# INDICATOR_DISPLAY.net
KiCad netlist of a schematic drawn in Altium Designer
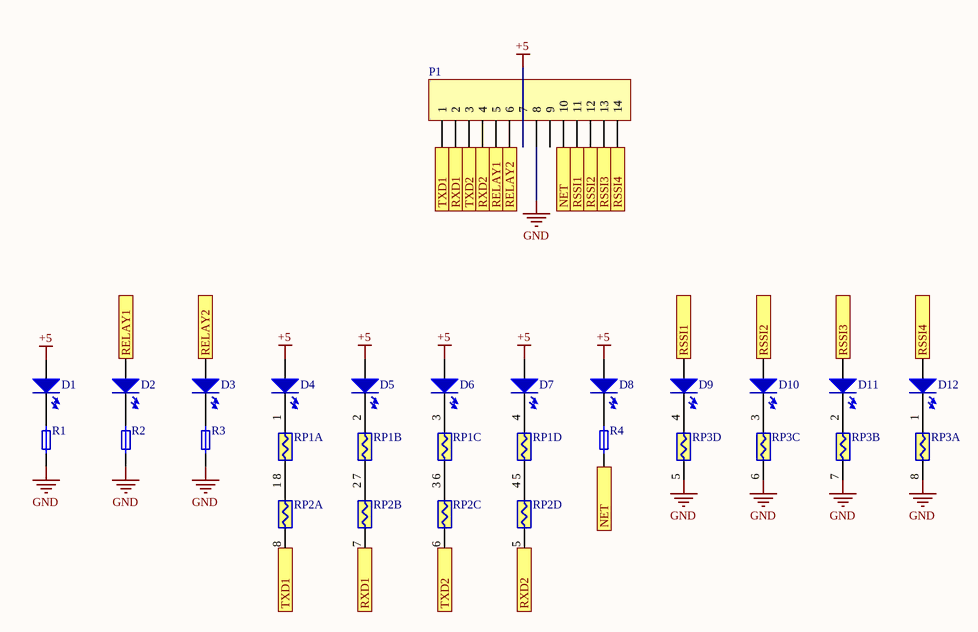
[diagram p0: INDICATOR DISPLAY.SchDoc]

(export (version "E")
  (design (tool "Eeschema 10.0.6"))
  (components
    (comp (ref "D1")
      (value "SMD LED")
      (footprint "LED RED 3MM S")
      (libsource (lib "MyLibrary") (part "LED SMD"))
    )
    (comp (ref "D2")
      (value "SMD LED")
      (footprint "LED RED 3MM S")
      (libsource (lib "MyLibrary") (part "LED SMD"))
    )
    (comp (ref "D3")
      (value "SMD LED")
      (footprint "LED RED 3MM S")
      (libsource (lib "MyLibrary") (part "LED SMD"))
    )
    (comp (ref "D4")
      (value "SMD LED")
      (footprint "LED RED 3MM S")
      (libsource (lib "MyLibrary") (part "LED SMD"))
    )
    (comp (ref "D5")
      (value "SMD LED")
      (footprint "LED RED 3MM S")
      (libsource (lib "MyLibrary") (part "LED SMD"))
    )
    (comp (ref "D6")
      (value "SMD LED")
      (footprint "LED RED 3MM S")
      (libsource (lib "MyLibrary") (part "LED SMD"))
    )
    (comp (ref "D7")
      (value "SMD LED")
      (footprint "LED RED 3MM S")
      (libsource (lib "MyLibrary") (part "LED SMD"))
    )
    (comp (ref "D8")
      (value "SMD LED")
      (footprint "LED RED 3MM S")
      (libsource (lib "MyLibrary") (part "LED SMD"))
    )
    (comp (ref "D9")
      (value "SMD LED")
      (footprint "LED RED 3MM S")
      (libsource (lib "MyLibrary") (part "LED SMD"))
    )
    (comp (ref "D10")
      (value "SMD LED")
      (footprint "LED RED 3MM S")
      (libsource (lib "MyLibrary") (part "LED SMD"))
    )
    (comp (ref "D11")
      (value "SMD LED")
      (footprint "LED RED 3MM S")
      (libsource (lib "MyLibrary") (part "LED SMD"))
    )
    (comp (ref "D12")
      (value "SMD LED")
      (footprint "LED RED 3MM S")
      (libsource (lib "MyLibrary") (part "LED SMD"))
    )
    (comp (ref "P1")
      (value "Header 14")
      (footprint "HDR1X14")
      (description "Header, 14-Pin")
      (fields (field (name "PUBLISHER") "Altium Limited"))
      (libsource (lib "Miscellaneous Connectors") (part "Header 14"))
    )
    (comp (ref "R1")
      (value "PTS120630V012")
      (footprint "1206 Resistor")
      (libsource (lib "MyLibrary") (part "PTS120630V012"))
    )
    (comp (ref "R2")
      (value "PTS120630V012")
      (footprint "1206 Resistor")
      (libsource (lib "MyLibrary") (part "PTS120630V012"))
    )
    (comp (ref "R3")
      (value "PTS120630V012")
      (footprint "1206 Resistor")
      (libsource (lib "MyLibrary") (part "PTS120630V012"))
    )
    (comp (ref "R4")
      (value "PTS120630V012")
      (footprint "1206 Resistor")
      (libsource (lib "MyLibrary") (part "PTS120630V012"))
    )
    (comp (ref "RP1")
      (value "Resistor Pack 4x1")
      (footprint "RP4x0603")
      (libsource (lib "MyLibrary") (part "Resistor Pack 4*1"))
    )
    (comp (ref "RP2")
      (value "Resistor Pack 4x1")
      (footprint "RP4x0603")
      (libsource (lib "MyLibrary") (part "Resistor Pack 4*1"))
    )
    (comp (ref "RP3")
      (value "Resistor Pack 4x1")
      (footprint "RP4x0603")
      (libsource (lib "MyLibrary") (part "Resistor Pack 4*1"))
    )
  )
  (nets
    (net (code "1") (name "+5") (class "Default")
      (node (ref "D4") (pin "1") (pinfunction "A_1") (pintype "passive"))
      (node (ref "D5") (pin "1") (pinfunction "A_1") (pintype "passive"))
      (node (ref "D6") (pin "1") (pinfunction "A_1") (pintype "passive"))
      (node (ref "D7") (pin "1") (pinfunction "A_1") (pintype "passive"))
      (node (ref "D8") (pin "1") (pinfunction "A_1") (pintype "passive"))
      (node (ref "P1") (pin "7") (pinfunction "7_7") (pintype "passive"))
    )
    (net (code "2") (name "/NET") (class "Default")
      (node (ref "P1") (pin "10") (pinfunction "10_10") (pintype "passive"))
      (node (ref "R4") (pin "1") (pintype "passive"))
    )
    (net (code "3") (name "/RELAY1") (class "Default")
      (node (ref "D2") (pin "1") (pinfunction "A_1") (pintype "passive"))
      (node (ref "P1") (pin "5") (pinfunction "5_5") (pintype "passive"))
    )
    (net (code "4") (name "/RELAY2") (class "Default")
      (node (ref "D3") (pin "1") (pinfunction "A_1") (pintype "passive"))
      (node (ref "P1") (pin "6") (pinfunction "6_6") (pintype "passive"))
    )
    (net (code "5") (name "/RSSI1") (class "Default")
      (node (ref "D9") (pin "1") (pinfunction "A_1") (pintype "passive"))
      (node (ref "P1") (pin "11") (pinfunction "11_11") (pintype "passive"))
    )
    (net (code "6") (name "/RSSI2") (class "Default")
      (node (ref "D10") (pin "1") (pinfunction "A_1") (pintype "passive"))
      (node (ref "P1") (pin "12") (pinfunction "12_12") (pintype "passive"))
    )
    (net (code "7") (name "/RSSI3") (class "Default")
      (node (ref "D11") (pin "1") (pinfunction "A_1") (pintype "passive"))
      (node (ref "P1") (pin "13") (pinfunction "13_13") (pintype "passive"))
    )
    (net (code "8") (name "/RSSI4") (class "Default")
      (node (ref "D12") (pin "1") (pinfunction "A_1") (pintype "passive"))
      (node (ref "P1") (pin "14") (pinfunction "14_14") (pintype "passive"))
    )
    (net (code "9") (name "/RXD1") (class "Default")
      (node (ref "P1") (pin "2") (pinfunction "2_2") (pintype "passive"))
      (node (ref "RP2") (pin "7") (pinfunction "7_7") (pintype "passive"))
    )
    (net (code "10") (name "/RXD2") (class "Default")
      (node (ref "P1") (pin "4") (pinfunction "4_4") (pintype "passive"))
      (node (ref "RP2") (pin "5") (pinfunction "5_5") (pintype "passive"))
    )
    (net (code "11") (name "/TXD1") (class "Default")
      (node (ref "P1") (pin "1") (pinfunction "1_1") (pintype "passive"))
      (node (ref "RP2") (pin "8") (pinfunction "8_8") (pintype "passive"))
    )
    (net (code "12") (name "/TXD2") (class "Default")
      (node (ref "P1") (pin "3") (pinfunction "3_3") (pintype "passive"))
      (node (ref "RP2") (pin "6") (pinfunction "6_6") (pintype "passive"))
    )
    (net (code "13") (name "GND") (class "Default")
      (node (ref "P1") (pin "8") (pinfunction "8_8") (pintype "passive"))
      (node (ref "R1") (pin "1") (pintype "passive"))
      (node (ref "R2") (pin "1") (pintype "passive"))
      (node (ref "R3") (pin "1") (pintype "passive"))
      (node (ref "RP3") (pin "5") (pinfunction "5_5") (pintype "passive"))
      (node (ref "RP3") (pin "6") (pinfunction "6_6") (pintype "passive"))
      (node (ref "RP3") (pin "7") (pinfunction "7_7") (pintype "passive"))
      (node (ref "RP3") (pin "8") (pinfunction "8_8") (pintype "passive"))
    )
    (net (code "14") (name "Net-(D1-K)") (class "Default")
      (node (ref "D1") (pin "2") (pinfunction "K_2") (pintype "passive"))
      (node (ref "R1") (pin "2") (pintype "passive"))
    )
    (net (code "15") (name "Net-(D2-K)") (class "Default")
      (node (ref "D2") (pin "2") (pinfunction "K_2") (pintype "passive"))
      (node (ref "R2") (pin "2") (pintype "passive"))
    )
    (net (code "16") (name "Net-(D3-K)") (class "Default")
      (node (ref "D3") (pin "2") (pinfunction "K_2") (pintype "passive"))
      (node (ref "R3") (pin "2") (pintype "passive"))
    )
    (net (code "17") (name "Net-(D4-K)") (class "Default")
      (node (ref "D4") (pin "2") (pinfunction "K_2") (pintype "passive"))
      (node (ref "RP1") (pin "1") (pinfunction "1_1") (pintype "passive"))
    )
    (net (code "18") (name "Net-(D5-K)") (class "Default")
      (node (ref "D5") (pin "2") (pinfunction "K_2") (pintype "passive"))
      (node (ref "RP1") (pin "2") (pinfunction "2_2") (pintype "passive"))
    )
    (net (code "19") (name "Net-(D6-K)") (class "Default")
      (node (ref "D6") (pin "2") (pinfunction "K_2") (pintype "passive"))
      (node (ref "RP1") (pin "3") (pinfunction "3_3") (pintype "passive"))
    )
    (net (code "20") (name "Net-(D7-K)") (class "Default")
      (node (ref "D7") (pin "2") (pinfunction "K_2") (pintype "passive"))
      (node (ref "RP1") (pin "4") (pinfunction "4_4") (pintype "passive"))
    )
    (net (code "21") (name "Net-(D8-K)") (class "Default")
      (node (ref "D8") (pin "2") (pinfunction "K_2") (pintype "passive"))
      (node (ref "R4") (pin "2") (pintype "passive"))
    )
    (net (code "22") (name "Net-(D9-K)") (class "Default")
      (node (ref "D9") (pin "2") (pinfunction "K_2") (pintype "passive"))
      (node (ref "RP3") (pin "4") (pinfunction "4_4") (pintype "passive"))
    )
    (net (code "23") (name "Net-(D10-K)") (class "Default")
      (node (ref "D10") (pin "2") (pinfunction "K_2") (pintype "passive"))
      (node (ref "RP3") (pin "3") (pinfunction "3_3") (pintype "passive"))
    )
    (net (code "24") (name "Net-(D11-K)") (class "Default")
      (node (ref "D11") (pin "2") (pinfunction "K_2") (pintype "passive"))
      (node (ref "RP3") (pin "2") (pinfunction "2_2") (pintype "passive"))
    )
    (net (code "25") (name "Net-(D12-K)") (class "Default")
      (node (ref "D12") (pin "2") (pinfunction "K_2") (pintype "passive"))
      (node (ref "RP3") (pin "1") (pinfunction "1_1") (pintype "passive"))
    )
    (net (code "26") (name "Net-(RP1-Pad5)") (class "Default")
      (node (ref "RP1") (pin "5") (pinfunction "5_5") (pintype "passive"))
      (node (ref "RP2") (pin "4") (pinfunction "4_4") (pintype "passive"))
    )
    (net (code "27") (name "Net-(RP1-Pad6)") (class "Default")
      (node (ref "RP1") (pin "6") (pinfunction "6_6") (pintype "passive"))
      (node (ref "RP2") (pin "3") (pinfunction "3_3") (pintype "passive"))
    )
    (net (code "28") (name "Net-(RP1-Pad7)") (class "Default")
      (node (ref "RP1") (pin "7") (pinfunction "7_7") (pintype "passive"))
      (node (ref "RP2") (pin "2") (pinfunction "2_2") (pintype "passive"))
    )
    (net (code "29") (name "Net-(RP1-Pad8)") (class "Default")
      (node (ref "RP1") (pin "8") (pinfunction "8_8") (pintype "passive"))
      (node (ref "RP2") (pin "1") (pinfunction "1_1") (pintype "passive"))
    )
    (net (code "30") (name "unconnected-(D1-A-Pad1)") (class "Default")
      (node (ref "D1") (pin "1") (pinfunction "A_1") (pintype "passive"))
    )
    (net (code "31") (name "unconnected-(P1-Pad9)") (class "Default")
      (node (ref "P1") (pin "9") (pinfunction "9_9") (pintype "passive"))
    )
  )
)
